# tinyx_core32_v0.net
KiCad netlist of a schematic drawn in EAGLE
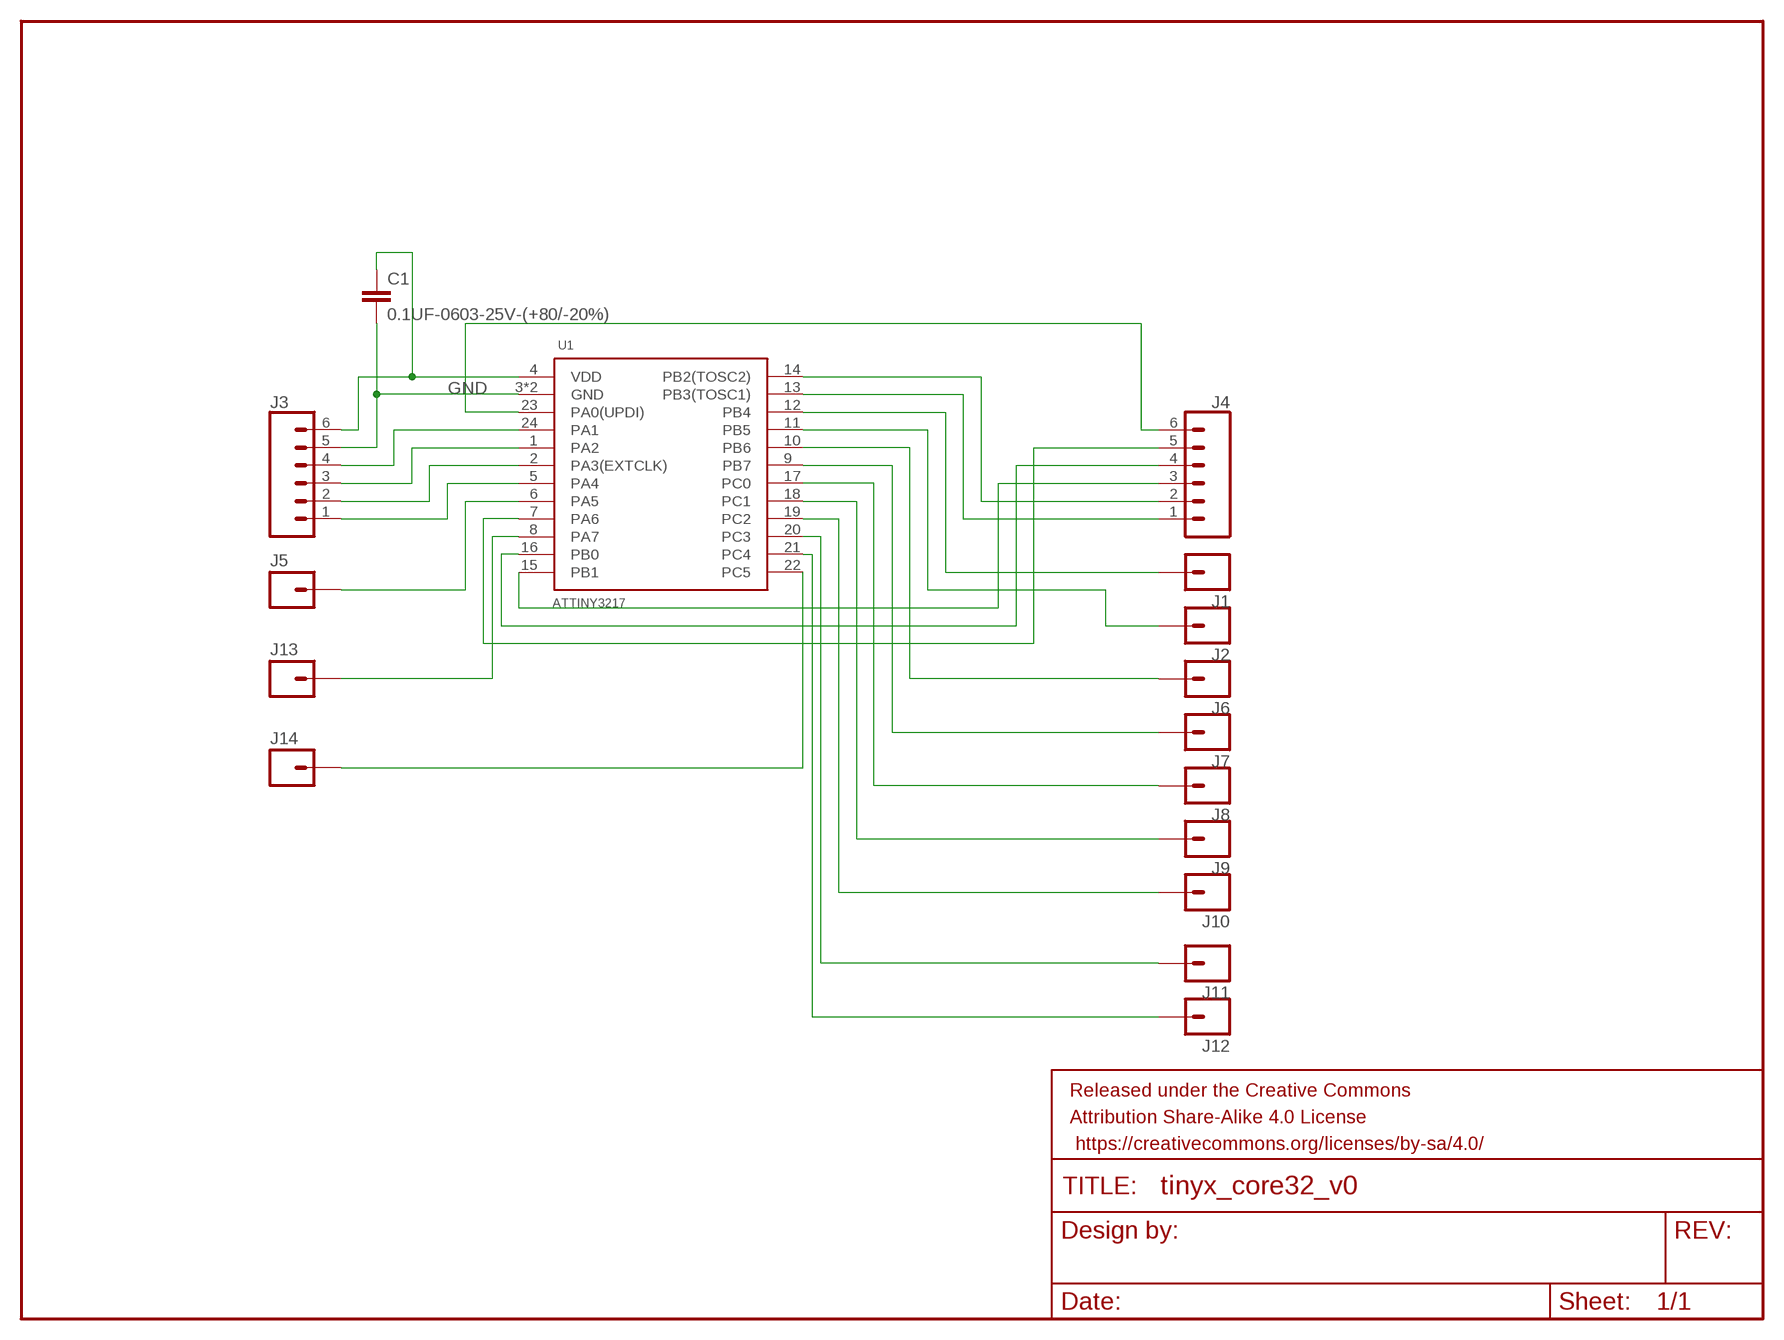
[diagram p0: schematic, sheet 1]

(export (version "E")
  (design (tool "Eeschema 10.0.6"))
  (components
    (comp (ref "C1")
      (value "0.1UF-0603-25V-(+80/-20%)")
      (footprint "eagle-import:0603")
      (libsource (lib "eagle-import") (part "0.1UF-0603-25V-(+80/-20%)"))
    )
    (comp (ref "FRAME1")
      (value "FRAME-LETTER")
      (footprint "eagle-import:CREATIVE_COMMONS")
      (libsource (lib "eagle-import") (part "FRAME-LETTER"))
    )
    (comp (ref "J1")
      (value "M01TINY")
      (footprint "eagle-import:1X01_TINY")
      (libsource (lib "eagle-import") (part "M01TINY"))
    )
    (comp (ref "J2")
      (value "M01TINY")
      (footprint "eagle-import:1X01_TINY")
      (libsource (lib "eagle-import") (part "M01TINY"))
    )
    (comp (ref "J3")
      (value "CONN_06NO_SILK_NO_POP")
      (footprint "eagle-import:1X06_NO_SILK")
      (libsource (lib "eagle-import") (part "CONN_06NO_SILK_NO_POP"))
    )
    (comp (ref "J4")
      (value "CONN_06NO_SILK_NO_POP")
      (footprint "eagle-import:1X06_NO_SILK")
      (libsource (lib "eagle-import") (part "CONN_06NO_SILK_NO_POP"))
    )
    (comp (ref "J5")
      (value "M01TINY")
      (footprint "eagle-import:1X01_TINY")
      (libsource (lib "eagle-import") (part "M01TINY"))
    )
    (comp (ref "J6")
      (value "M01TINY")
      (footprint "eagle-import:1X01_TINY")
      (libsource (lib "eagle-import") (part "M01TINY"))
    )
    (comp (ref "J7")
      (value "M01TINY")
      (footprint "eagle-import:1X01_TINY")
      (libsource (lib "eagle-import") (part "M01TINY"))
    )
    (comp (ref "J8")
      (value "M01TINY")
      (footprint "eagle-import:1X01_TINY")
      (libsource (lib "eagle-import") (part "M01TINY"))
    )
    (comp (ref "J9")
      (value "M01TINY")
      (footprint "eagle-import:1X01_TINY")
      (libsource (lib "eagle-import") (part "M01TINY"))
    )
    (comp (ref "J10")
      (value "M01TINY")
      (footprint "eagle-import:1X01_TINY")
      (libsource (lib "eagle-import") (part "M01TINY"))
    )
    (comp (ref "J11")
      (value "M01TINY")
      (footprint "eagle-import:1X01_TINY")
      (libsource (lib "eagle-import") (part "M01TINY"))
    )
    (comp (ref "J12")
      (value "M01TINY")
      (footprint "eagle-import:1X01_TINY")
      (libsource (lib "eagle-import") (part "M01TINY"))
    )
    (comp (ref "J13")
      (value "M01TINY")
      (footprint "eagle-import:1X01_TINY")
      (libsource (lib "eagle-import") (part "M01TINY"))
    )
    (comp (ref "J14")
      (value "M01TINY")
      (footprint "eagle-import:1X01_TINY")
      (libsource (lib "eagle-import") (part "M01TINY"))
    )
    (comp (ref "U1")
      (value "ATTINY3217")
      (footprint "eagle-import:VQFN-24-N")
      (libsource (lib "eagle-import") (part "ATTINY3217"))
    )
  )
  (nets
    (net (code "1") (name "/GND") (class "Default")
      (node (ref "C1") (pin "2") (pinfunction "2_2") (pintype "passive"))
      (node (ref "J3") (pin "5") (pinfunction "5_5") (pintype "passive"))
      (node (ref "U1") (pin "3") (pinfunction "GND_3") (pintype "bidirectional"))
      (node (ref "U1") (pin "P$1") (pinfunction "GND_P$1") (pintype "bidirectional"))
    )
    (net (code "2") (name "Net-(J1-1)") (class "Default")
      (node (ref "J1") (pin "P$1") (pinfunction "1_P$1") (pintype "passive"))
      (node (ref "U1") (pin "12") (pinfunction "PB4_12") (pintype "bidirectional"))
    )
    (net (code "3") (name "Net-(J2-1)") (class "Default")
      (node (ref "J2") (pin "P$1") (pinfunction "1_P$1") (pintype "passive"))
      (node (ref "U1") (pin "11") (pinfunction "PB5_11") (pintype "bidirectional"))
    )
    (net (code "4") (name "Net-(J5-1)") (class "Default")
      (node (ref "J5") (pin "P$1") (pinfunction "1_P$1") (pintype "passive"))
      (node (ref "U1") (pin "6") (pinfunction "PA5_6") (pintype "bidirectional"))
    )
    (net (code "5") (name "Net-(J6-1)") (class "Default")
      (node (ref "J6") (pin "P$1") (pinfunction "1_P$1") (pintype "passive"))
      (node (ref "U1") (pin "10") (pinfunction "PB6_10") (pintype "bidirectional"))
    )
    (net (code "6") (name "Net-(J7-1)") (class "Default")
      (node (ref "J7") (pin "P$1") (pinfunction "1_P$1") (pintype "passive"))
      (node (ref "U1") (pin "9") (pinfunction "PB7_9") (pintype "bidirectional"))
    )
    (net (code "7") (name "Net-(J8-1)") (class "Default")
      (node (ref "J8") (pin "P$1") (pinfunction "1_P$1") (pintype "passive"))
      (node (ref "U1") (pin "17") (pinfunction "PC0_17") (pintype "bidirectional"))
    )
    (net (code "8") (name "Net-(J9-1)") (class "Default")
      (node (ref "J9") (pin "P$1") (pinfunction "1_P$1") (pintype "passive"))
      (node (ref "U1") (pin "18") (pinfunction "PC1_18") (pintype "bidirectional"))
    )
    (net (code "9") (name "Net-(J10-1)") (class "Default")
      (node (ref "J10") (pin "P$1") (pinfunction "1_P$1") (pintype "passive"))
      (node (ref "U1") (pin "19") (pinfunction "PC2_19") (pintype "bidirectional"))
    )
    (net (code "10") (name "Net-(J11-1)") (class "Default")
      (node (ref "J11") (pin "P$1") (pinfunction "1_P$1") (pintype "passive"))
      (node (ref "U1") (pin "20") (pinfunction "PC3_20") (pintype "bidirectional"))
    )
    (net (code "11") (name "Net-(J12-1)") (class "Default")
      (node (ref "J12") (pin "P$1") (pinfunction "1_P$1") (pintype "passive"))
      (node (ref "U1") (pin "21") (pinfunction "PC4_21") (pintype "bidirectional"))
    )
    (net (code "12") (name "Net-(J13-1)") (class "Default")
      (node (ref "J13") (pin "P$1") (pinfunction "1_P$1") (pintype "passive"))
      (node (ref "U1") (pin "8") (pinfunction "PA7_8") (pintype "bidirectional"))
    )
    (net (code "13") (name "Net-(J14-1)") (class "Default")
      (node (ref "J14") (pin "P$1") (pinfunction "1_P$1") (pintype "passive"))
      (node (ref "U1") (pin "22") (pinfunction "PC5_22") (pintype "bidirectional"))
    )
    (net (code "14") (name "Net-(U1-PA0(UPDI))") (class "Default")
      (node (ref "J4") (pin "6") (pinfunction "6_6") (pintype "passive"))
      (node (ref "U1") (pin "23") (pinfunction "PA0(UPDI)_23") (pintype "bidirectional"))
    )
    (net (code "15") (name "Net-(U1-PA1)") (class "Default")
      (node (ref "J3") (pin "4") (pinfunction "4_4") (pintype "passive"))
      (node (ref "U1") (pin "24") (pinfunction "PA1_24") (pintype "bidirectional"))
    )
    (net (code "16") (name "Net-(U1-PA2)") (class "Default")
      (node (ref "J3") (pin "3") (pinfunction "3_3") (pintype "passive"))
      (node (ref "U1") (pin "1") (pinfunction "PA2_1") (pintype "bidirectional"))
    )
    (net (code "17") (name "Net-(U1-PA3(EXTCLK))") (class "Default")
      (node (ref "J3") (pin "2") (pinfunction "2_2") (pintype "passive"))
      (node (ref "U1") (pin "2") (pinfunction "PA3(EXTCLK)_2") (pintype "bidirectional"))
    )
    (net (code "18") (name "Net-(U1-PA4)") (class "Default")
      (node (ref "J3") (pin "1") (pinfunction "1_1") (pintype "passive"))
      (node (ref "U1") (pin "5") (pinfunction "PA4_5") (pintype "bidirectional"))
    )
    (net (code "19") (name "Net-(U1-PA6)") (class "Default")
      (node (ref "J4") (pin "5") (pinfunction "5_5") (pintype "passive"))
      (node (ref "U1") (pin "7") (pinfunction "PA6_7") (pintype "bidirectional"))
    )
    (net (code "20") (name "Net-(U1-PB0)") (class "Default")
      (node (ref "J4") (pin "4") (pinfunction "4_4") (pintype "passive"))
      (node (ref "U1") (pin "16") (pinfunction "PB0_16") (pintype "bidirectional"))
    )
    (net (code "21") (name "Net-(U1-PB1)") (class "Default")
      (node (ref "J4") (pin "3") (pinfunction "3_3") (pintype "passive"))
      (node (ref "U1") (pin "15") (pinfunction "PB1_15") (pintype "bidirectional"))
    )
    (net (code "22") (name "Net-(U1-PB2(TOSC2))") (class "Default")
      (node (ref "J4") (pin "2") (pinfunction "2_2") (pintype "passive"))
      (node (ref "U1") (pin "14") (pinfunction "PB2(TOSC2)_14") (pintype "bidirectional"))
    )
    (net (code "23") (name "Net-(U1-PB3(TOSC1))") (class "Default")
      (node (ref "J4") (pin "1") (pinfunction "1_1") (pintype "passive"))
      (node (ref "U1") (pin "13") (pinfunction "PB3(TOSC1)_13") (pintype "bidirectional"))
    )
    (net (code "24") (name "Net-(U1-VDD)") (class "Default")
      (node (ref "C1") (pin "1") (pinfunction "1_1") (pintype "passive"))
      (node (ref "J3") (pin "6") (pinfunction "6_6") (pintype "passive"))
      (node (ref "U1") (pin "4") (pinfunction "VDD_4") (pintype "bidirectional"))
    )
  )
)
